# Drone.net
KiCad netlist of a schematic drawn in EAGLE
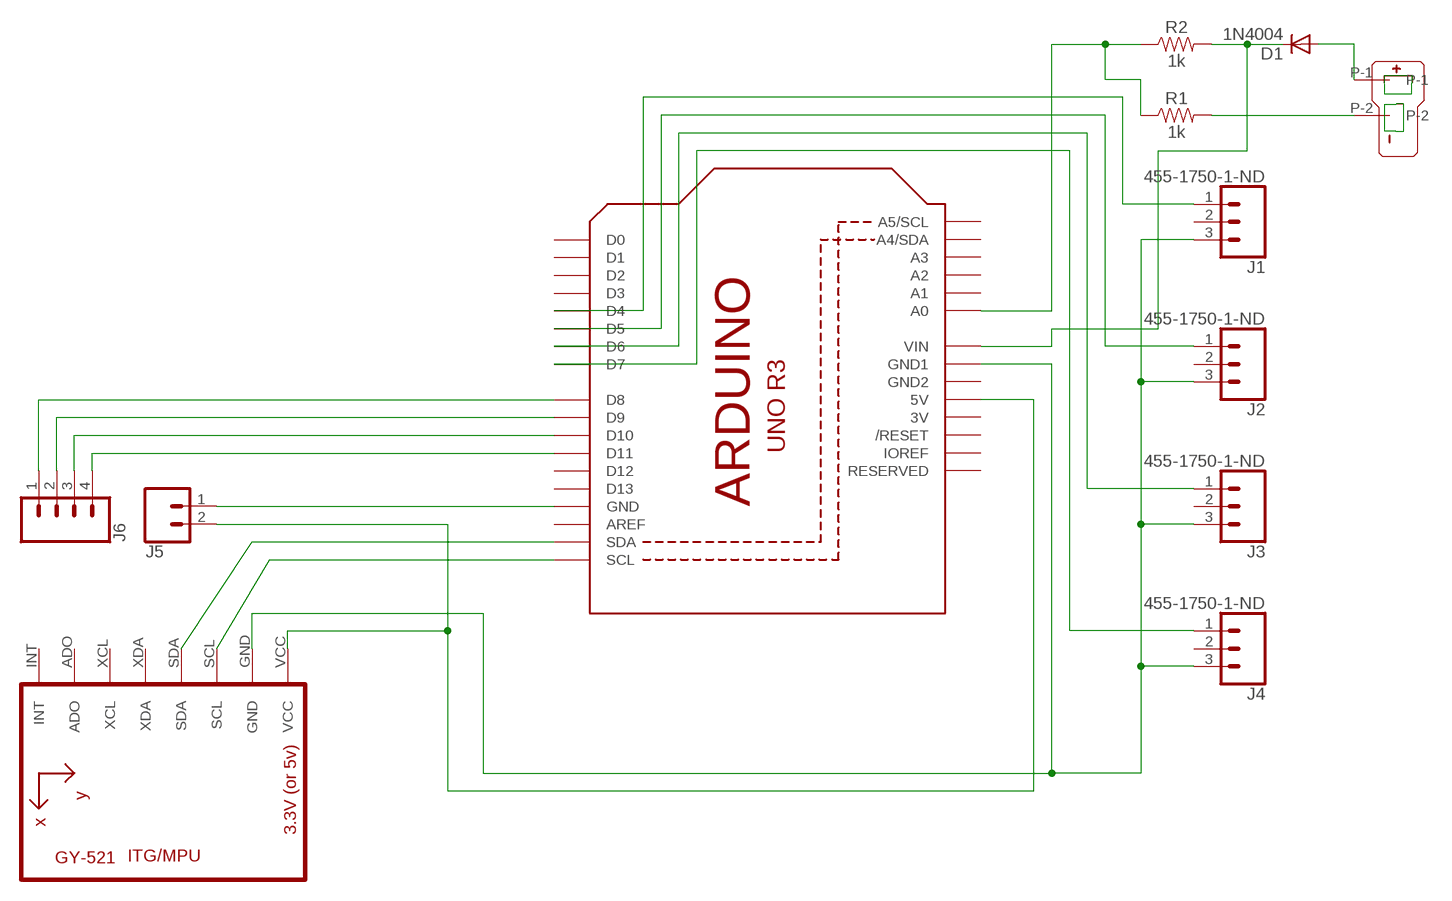
[diagram p0: schematic, sheet 1]

(export (version "E")
  (design (tool "Eeschema 10.0.6"))
  (components
    (comp (ref "D1")
      (value "1N4004")
      (footprint "eagle-import:DO41-10")
      (libsource (lib "eagle-import") (part "1N4004"))
    )
    (comp (ref "J1")
      (value "455-1750-1-ND")
      (footprint "eagle-import:1X03")
      (libsource (lib "eagle-import") (part "CONN_03"))
    )
    (comp (ref "J2")
      (value "455-1750-1-ND")
      (footprint "eagle-import:1X03")
      (libsource (lib "eagle-import") (part "CONN_03"))
    )
    (comp (ref "J3")
      (value "455-1750-1-ND")
      (footprint "eagle-import:1X03")
      (libsource (lib "eagle-import") (part "CONN_03"))
    )
    (comp (ref "J4")
      (value "455-1750-1-ND")
      (footprint "eagle-import:1X03")
      (libsource (lib "eagle-import") (part "CONN_03"))
    )
    (comp (ref "J5")
      (value "CONN_02")
      (footprint "eagle-import:1X02")
      (libsource (lib "eagle-import") (part "CONN_02"))
    )
    (comp (ref "J6")
      (value "CONN_04JST-PTH")
      (footprint "eagle-import:JST-4-PTH")
      (libsource (lib "eagle-import") (part "CONN_04JST-PTH"))
    )
    (comp (ref "R1")
      (value "1k")
      (footprint "eagle-import:AXIAL-0.1-KIT")
      (libsource (lib "eagle-import") (part "1KOHM-VERT_KIT-1/4W-1%"))
    )
    (comp (ref "R2")
      (value "1k")
      (footprint "eagle-import:AXIAL-0.1-KIT")
      (libsource (lib "eagle-import") (part "1KOHM-VERT_KIT-1/4W-1%"))
    )
    (comp (ref "U$1")
      (value "T-PLUG_CONNECTOR")
      (footprint "eagle-import:T_PLUG_CONNECTOR")
      (libsource (lib "eagle-import") (part "T-PLUG_CONNECTOR"))
    )
    (comp (ref "U1")
      (value "ARDUINOR3-BPLACE")
      (footprint "eagle-import:ARDUINOR3-BPLACE")
      (libsource (lib "eagle-import") (part "ARDUINOR3-BPLACE"))
    )
    (comp (ref "U2")
      (value "GY-521MPU6050")
      (footprint "eagle-import:GY-521")
      (libsource (lib "eagle-import") (part "GY-521MPU6050"))
    )
  )
  (nets
    (net (code "1") (name "/3V") (class "Default")
      (node (ref "U1") (pin "3V") (pinfunction "3V_3V") (pintype "power_in"))
    )
    (net (code "2") (name "/GND2") (class "Default")
      (node (ref "U1") (pin "GND2") (pinfunction "GND2_GND2") (pintype "power_in"))
    )
    (net (code "3") (name "Net-(D1-PadA)") (class "Default")
      (node (ref "D1") (pin "A") (pinfunction "A_A") (pintype "passive"))
      (node (ref "U$1") (pin "P-1") (pinfunction "P-1_P-1") (pintype "passive"))
    )
    (net (code "4") (name "Net-(J1-Pad1)") (class "Default")
      (node (ref "J1") (pin "1") (pinfunction "1_1") (pintype "passive"))
      (node (ref "U1") (pin "D4") (pinfunction "D4_D4") (pintype "bidirectional"))
    )
    (net (code "5") (name "Net-(J1-Pad3)") (class "Default")
      (node (ref "J1") (pin "3") (pinfunction "3_3") (pintype "passive"))
      (node (ref "J2") (pin "3") (pinfunction "3_3") (pintype "passive"))
      (node (ref "J3") (pin "3") (pinfunction "3_3") (pintype "passive"))
      (node (ref "J4") (pin "3") (pinfunction "3_3") (pintype "passive"))
      (node (ref "U1") (pin "GND1") (pinfunction "GND1_GND1") (pintype "power_in"))
      (node (ref "U2") (pin "GND") (pinfunction "GND_GND") (pintype "bidirectional"))
    )
    (net (code "6") (name "Net-(J2-Pad1)") (class "Default")
      (node (ref "J2") (pin "1") (pinfunction "1_1") (pintype "passive"))
      (node (ref "U1") (pin "D5") (pinfunction "D5_D5") (pintype "bidirectional"))
    )
    (net (code "7") (name "Net-(J3-Pad1)") (class "Default")
      (node (ref "J3") (pin "1") (pinfunction "1_1") (pintype "passive"))
      (node (ref "U1") (pin "D6") (pinfunction "D6_D6") (pintype "bidirectional"))
    )
    (net (code "8") (name "Net-(J4-Pad1)") (class "Default")
      (node (ref "J4") (pin "1") (pinfunction "1_1") (pintype "passive"))
      (node (ref "U1") (pin "D7") (pinfunction "D7_D7") (pintype "bidirectional"))
    )
    (net (code "9") (name "Net-(J5-Pad1)") (class "Default")
      (node (ref "J5") (pin "1") (pinfunction "1_1") (pintype "passive"))
      (node (ref "U1") (pin "GND") (pinfunction "GND_GND") (pintype "power_in"))
    )
    (net (code "10") (name "Net-(J5-Pad2)") (class "Default")
      (node (ref "J5") (pin "2") (pinfunction "2_2") (pintype "passive"))
      (node (ref "U1") (pin "5V") (pinfunction "5V_5V") (pintype "power_in"))
      (node (ref "U2") (pin "VCC") (pinfunction "VCC_VCC") (pintype "bidirectional"))
    )
    (net (code "11") (name "Net-(J6-Pad1)") (class "Default")
      (node (ref "J6") (pin "1") (pinfunction "1_1") (pintype "passive"))
      (node (ref "U1") (pin "D8") (pinfunction "D8_D8") (pintype "bidirectional"))
    )
    (net (code "12") (name "Net-(J6-Pad2)") (class "Default")
      (node (ref "J6") (pin "2") (pinfunction "2_2") (pintype "passive"))
      (node (ref "U1") (pin "D9") (pinfunction "D9_D9") (pintype "bidirectional"))
    )
    (net (code "13") (name "Net-(J6-Pad3)") (class "Default")
      (node (ref "J6") (pin "3") (pinfunction "3_3") (pintype "passive"))
      (node (ref "U1") (pin "D10") (pinfunction "D10_D10") (pintype "bidirectional"))
    )
    (net (code "14") (name "Net-(J6-Pad4)") (class "Default")
      (node (ref "J6") (pin "4") (pinfunction "4_4") (pintype "passive"))
      (node (ref "U1") (pin "D11") (pinfunction "D11_D11") (pintype "bidirectional"))
    )
    (net (code "15") (name "Net-(R1-1)") (class "Default")
      (node (ref "R1") (pin "P$1") (pinfunction "1_P$1") (pintype "passive"))
      (node (ref "R2") (pin "P$1") (pinfunction "1_P$1") (pintype "passive"))
      (node (ref "U1") (pin "A0") (pinfunction "A0_A0") (pintype "bidirectional"))
    )
    (net (code "16") (name "Net-(R1-2)") (class "Default")
      (node (ref "R1") (pin "P$2") (pinfunction "2_P$2") (pintype "passive"))
      (node (ref "U$1") (pin "P-2") (pinfunction "P-2_P-2") (pintype "passive"))
    )
    (net (code "17") (name "Net-(R2-2)") (class "Default")
      (node (ref "D1") (pin "C") (pinfunction "C_C") (pintype "passive"))
      (node (ref "R2") (pin "P$2") (pinfunction "2_P$2") (pintype "passive"))
      (node (ref "U1") (pin "VIN") (pinfunction "VIN_VIN") (pintype "power_in"))
    )
    (net (code "18") (name "Net-(U1-PadSCL)") (class "Default")
      (node (ref "U1") (pin "SCL") (pinfunction "SCL_SCL") (pintype "bidirectional"))
      (node (ref "U2") (pin "SCL") (pinfunction "SCL_SCL") (pintype "bidirectional"))
    )
    (net (code "19") (name "Net-(U1-PadSDA)") (class "Default")
      (node (ref "U1") (pin "SDA") (pinfunction "SDA_SDA") (pintype "bidirectional"))
      (node (ref "U2") (pin "SDA") (pinfunction "SDA_SDA") (pintype "bidirectional"))
    )
    (net (code "20") (name "unconnected-(J1-Pad2)") (class "Default")
      (node (ref "J1") (pin "2") (pinfunction "2_2") (pintype "passive"))
    )
    (net (code "21") (name "unconnected-(J2-Pad2)") (class "Default")
      (node (ref "J2") (pin "2") (pinfunction "2_2") (pintype "passive"))
    )
    (net (code "22") (name "unconnected-(J3-Pad2)") (class "Default")
      (node (ref "J3") (pin "2") (pinfunction "2_2") (pintype "passive"))
    )
    (net (code "23") (name "unconnected-(J4-Pad2)") (class "Default")
      (node (ref "J4") (pin "2") (pinfunction "2_2") (pintype "passive"))
    )
    (net (code "24") (name "unconnected-(U1-A4{slash}SDA-PadA4)") (class "Default")
      (node (ref "U1") (pin "A4") (pinfunction "A4/SDA_A4") (pintype "bidirectional"))
    )
    (net (code "25") (name "unconnected-(U1-A5{slash}SCL-PadA5)") (class "Default")
      (node (ref "U1") (pin "A5") (pinfunction "A5/SCL_A5") (pintype "bidirectional"))
    )
    (net (code "26") (name "unconnected-(U1-PadA1)") (class "Default")
      (node (ref "U1") (pin "A1") (pinfunction "A1_A1") (pintype "bidirectional"))
    )
    (net (code "27") (name "unconnected-(U1-PadA2)") (class "Default")
      (node (ref "U1") (pin "A2") (pinfunction "A2_A2") (pintype "bidirectional"))
    )
    (net (code "28") (name "unconnected-(U1-PadA3)") (class "Default")
      (node (ref "U1") (pin "A3") (pinfunction "A3_A3") (pintype "bidirectional"))
    )
    (net (code "29") (name "unconnected-(U1-PadAREF)") (class "Default")
      (node (ref "U1") (pin "AREF") (pinfunction "AREF_AREF") (pintype "bidirectional"))
    )
    (net (code "30") (name "unconnected-(U1-PadD0)") (class "Default")
      (node (ref "U1") (pin "D0") (pinfunction "D0_D0") (pintype "bidirectional"))
    )
    (net (code "31") (name "unconnected-(U1-PadD1)") (class "Default")
      (node (ref "U1") (pin "D1") (pinfunction "D1_D1") (pintype "bidirectional"))
    )
    (net (code "32") (name "unconnected-(U1-PadD2)") (class "Default")
      (node (ref "U1") (pin "D2") (pinfunction "D2_D2") (pintype "bidirectional"))
    )
    (net (code "33") (name "unconnected-(U1-PadD3)") (class "Default")
      (node (ref "U1") (pin "D3") (pinfunction "D3_D3") (pintype "bidirectional"))
    )
    (net (code "34") (name "unconnected-(U1-PadD12)") (class "Default")
      (node (ref "U1") (pin "D12") (pinfunction "D12_D12") (pintype "bidirectional"))
    )
    (net (code "35") (name "unconnected-(U1-PadD13)") (class "Default")
      (node (ref "U1") (pin "D13") (pinfunction "D13_D13") (pintype "bidirectional"))
    )
    (net (code "36") (name "unconnected-(U1-PadIOREF)") (class "Default")
      (node (ref "U1") (pin "IOREF") (pinfunction "IOREF_IOREF") (pintype "output"))
    )
    (net (code "37") (name "unconnected-(U1-PadRESERVED)") (class "Default")
      (node (ref "U1") (pin "RESERVED") (pinfunction "RESERVED_RESERVED") (pintype "no_connect"))
    )
    (net (code "38") (name "unconnected-(U1-{slash}RESET-PadRESET)") (class "Default")
      (node (ref "U1") (pin "RESET") (pinfunction "/RESET_RESET") (pintype "bidirectional"))
    )
    (net (code "39") (name "unconnected-(U2-PadADO)") (class "Default")
      (node (ref "U2") (pin "ADO") (pinfunction "ADO_ADO") (pintype "bidirectional"))
    )
    (net (code "40") (name "unconnected-(U2-PadINT)") (class "Default")
      (node (ref "U2") (pin "INT") (pinfunction "INT_INT") (pintype "bidirectional"))
    )
    (net (code "41") (name "unconnected-(U2-PadXCL)") (class "Default")
      (node (ref "U2") (pin "XCL") (pinfunction "XCL_XCL") (pintype "bidirectional"))
    )
    (net (code "42") (name "unconnected-(U2-PadXDA)") (class "Default")
      (node (ref "U2") (pin "XDA") (pinfunction "XDA_XDA") (pintype "bidirectional"))
    )
  )
)
